# Eagle_Lecture.net
KiCad netlist of a schematic drawn in EAGLE
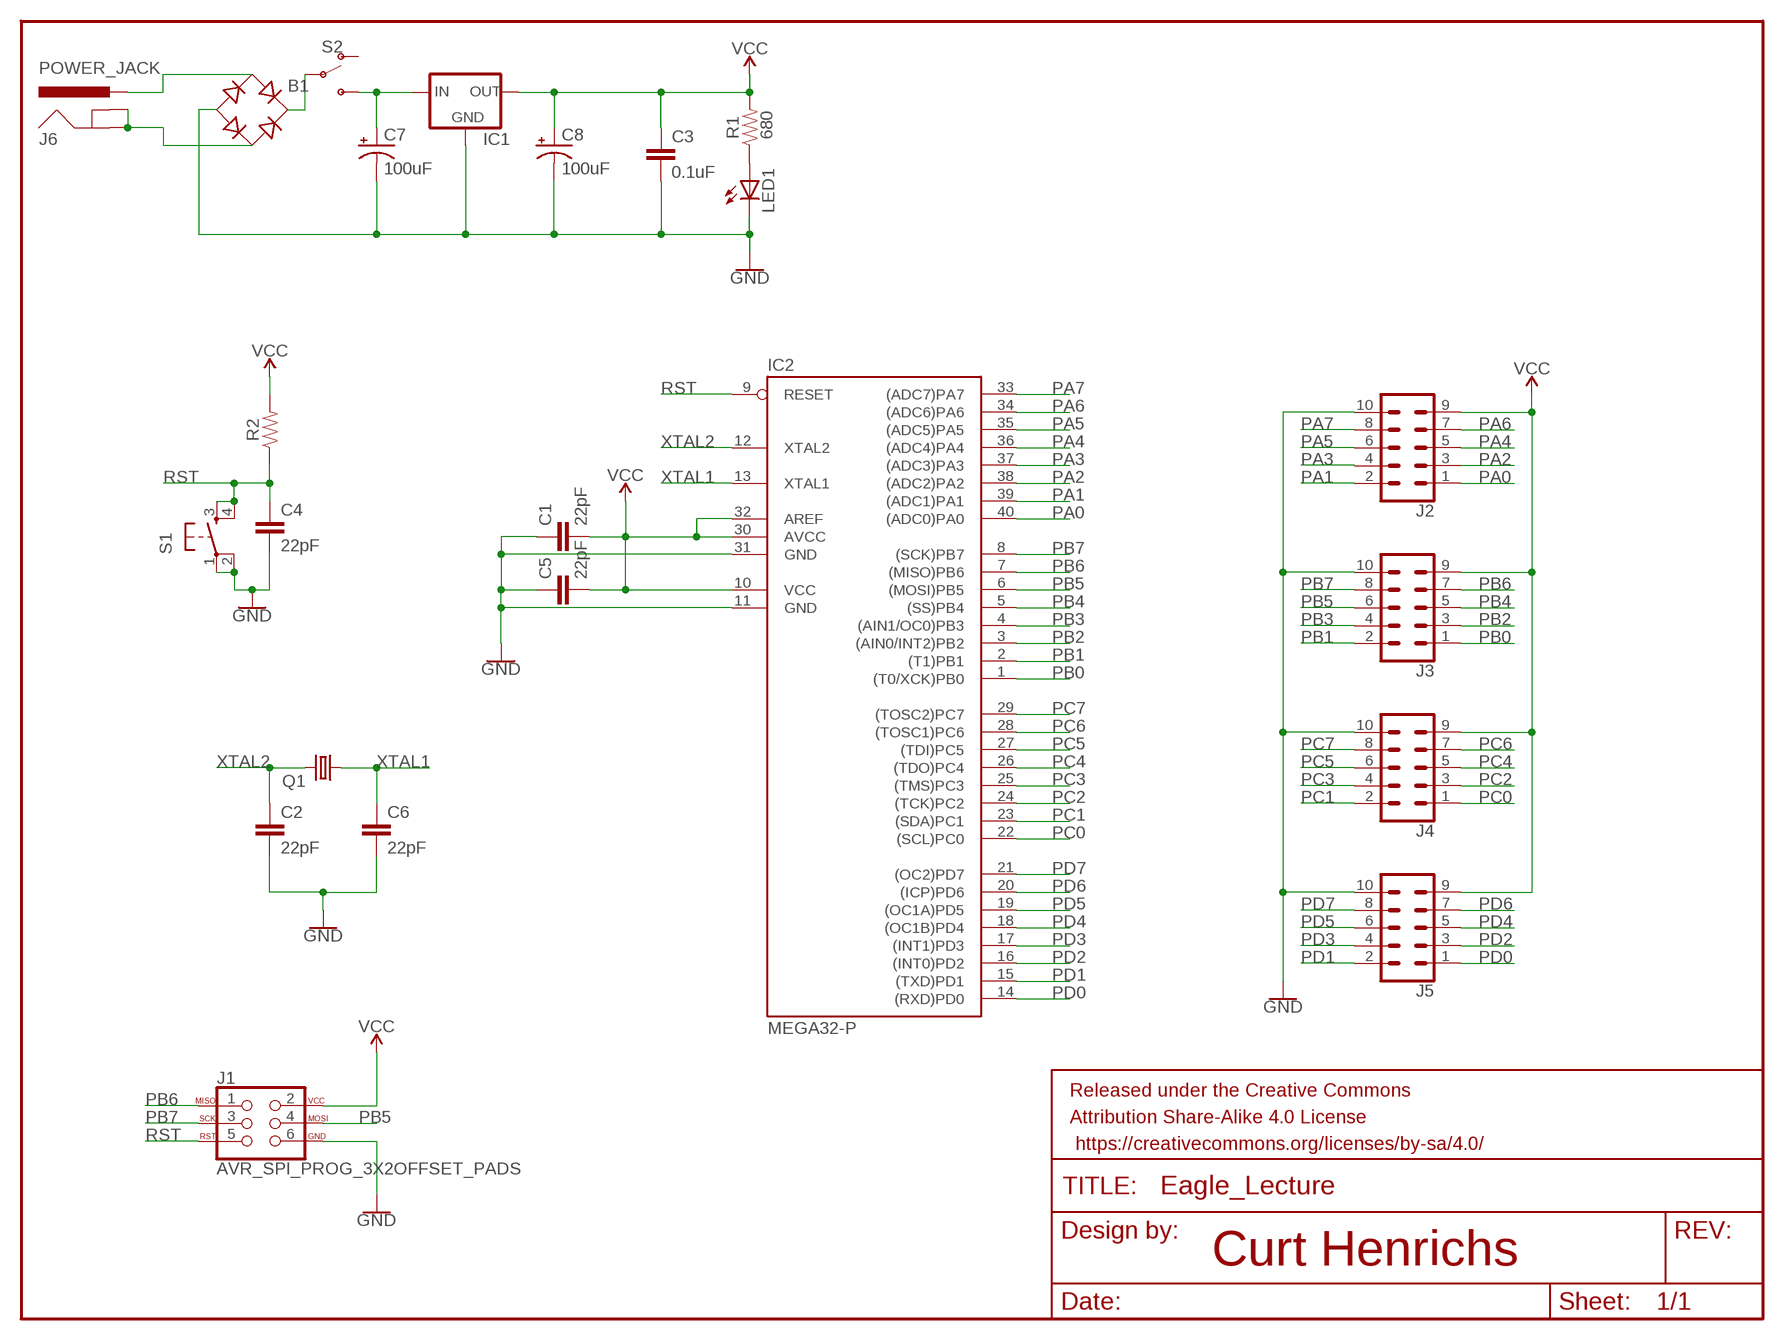
[diagram p0: schematic, sheet 1]

(export (version "E")
  (design (tool "Eeschema 10.0.6"))
  (components
    (comp (ref "B1")
      (value "B-DIL")
      (footprint "eagle-import:B-DIL")
      (libsource (lib "eagle-import") (part "B-DIL"))
    )
    (comp (ref "C1")
      (value "22pF")
      (footprint "eagle-import:CAP-PTH-2.54")
      (libsource (lib "eagle-import") (part "22PF-PTH-2.54MM-200V-5%"))
    )
    (comp (ref "C2")
      (value "22pF")
      (footprint "eagle-import:CAP-PTH-2.54")
      (libsource (lib "eagle-import") (part "22PF-PTH-2.54MM-200V-5%"))
    )
    (comp (ref "C3")
      (value "0.1uF")
      (footprint "eagle-import:CAP-PTH-2.54")
      (libsource (lib "eagle-import") (part "22PF-PTH-2.54MM-200V-5%"))
    )
    (comp (ref "C4")
      (value "22pF")
      (footprint "eagle-import:CAP-PTH-2.54")
      (libsource (lib "eagle-import") (part "22PF-PTH-2.54MM-200V-5%"))
    )
    (comp (ref "C5")
      (value "22pF")
      (footprint "eagle-import:CAP-PTH-2.54")
      (libsource (lib "eagle-import") (part "22PF-PTH-2.54MM-200V-5%"))
    )
    (comp (ref "C6")
      (value "22pF")
      (footprint "eagle-import:CAP-PTH-2.54")
      (libsource (lib "eagle-import") (part "22PF-PTH-2.54MM-200V-5%"))
    )
    (comp (ref "C7")
      (value "100uF")
      (footprint "eagle-import:CPOL-RADIAL-2.5MM-6.5MM")
      (libsource (lib "eagle-import") (part "100UF-POLAR-RADIAL-2.5MM-25V-20%"))
    )
    (comp (ref "C8")
      (value "100uF")
      (footprint "eagle-import:CPOL-RADIAL-2.5MM-6.5MM")
      (libsource (lib "eagle-import") (part "100UF-POLAR-RADIAL-2.5MM-25V-20%"))
    )
    (comp (ref "FRAME1")
      (value "FRAME-LETTER")
      (footprint "eagle-import:CREATIVE_COMMONS")
      (libsource (lib "eagle-import") (part "FRAME-LETTER"))
    )
    (comp (ref "IC1")
      (value "78MXXL")
      (footprint "eagle-import:78MXXL")
      (libsource (lib "eagle-import") (part "78MXXL"))
    )
    (comp (ref "IC2")
      (value "MEGA32-P")
      (footprint "eagle-import:DIL40")
      (fields (field (name "MPN") "ATMEGA32-16PU"))
      (libsource (lib "eagle-import") (part "MEGA32-P"))
    )
    (comp (ref "J1")
      (value "AVR_SPI_PROG_3X2OFFSET_PADS")
      (footprint "eagle-import:2X3_OFFSET")
      (libsource (lib "eagle-import") (part "AVR_SPI_PROG_3X2OFFSET_PADS"))
    )
    (comp (ref "J2")
      (value "CONN_05X2SHD")
      (footprint "eagle-import:2X5-SHROUDED")
      (libsource (lib "eagle-import") (part "CONN_05X2SHD"))
    )
    (comp (ref "J3")
      (value "CONN_05X2SHD")
      (footprint "eagle-import:2X5-SHROUDED")
      (libsource (lib "eagle-import") (part "CONN_05X2SHD"))
    )
    (comp (ref "J4")
      (value "CONN_05X2SHD")
      (footprint "eagle-import:2X5-SHROUDED")
      (libsource (lib "eagle-import") (part "CONN_05X2SHD"))
    )
    (comp (ref "J5")
      (value "CONN_05X2SHD")
      (footprint "eagle-import:2X5-SHROUDED")
      (libsource (lib "eagle-import") (part "CONN_05X2SHD"))
    )
    (comp (ref "J6")
      (value "POWER_JACK")
      (footprint "eagle-import:POWER_JACK_PTH")
      (libsource (lib "eagle-import") (part "POWER_JACK"))
    )
    (comp (ref "LED1")
      (value "LED3MM")
      (footprint "eagle-import:LED3MM")
      (libsource (lib "eagle-import") (part "LED3MM"))
    )
    (comp (ref "Q1")
      (value "CRYSTALHC49U-V")
      (footprint "eagle-import:HC49U-V")
      (libsource (lib "eagle-import") (part "CRYSTALHC49U-V"))
    )
    (comp (ref "R1")
      (value "680")
      (footprint "eagle-import:AXIAL-0.3")
      (libsource (lib "eagle-import") (part "RESISTORAXIAL-0.3"))
    )
    (comp (ref "R2")
      (value "RESISTORAXIAL-0.3")
      (footprint "eagle-import:AXIAL-0.3")
      (libsource (lib "eagle-import") (part "RESISTORAXIAL-0.3"))
    )
    (comp (ref "S1")
      (value "TAC_SWITCHPTH")
      (footprint "eagle-import:TACTILE-PTH")
      (libsource (lib "eagle-import") (part "TAC_SWITCHPTH"))
    )
    (comp (ref "S2")
      (value "SWITCH-SPDT-PTH-11.6X4.0MM")
      (footprint "eagle-import:SWITCH_SPDT_PTH_11.6X4.0MM")
      (libsource (lib "eagle-import") (part "SWITCH-SPDT-PTH-11.6X4.0MM"))
    )
  )
  (nets
    (net (code "1") (name "/PA0") (class "Default")
      (node (ref "IC2") (pin "40") (pinfunction "(ADC0)PA0_40") (pintype "bidirectional"))
      (node (ref "J2") (pin "1") (pinfunction "1_1") (pintype "passive"))
    )
    (net (code "2") (name "/PA1") (class "Default")
      (node (ref "IC2") (pin "39") (pinfunction "(ADC1)PA1_39") (pintype "bidirectional"))
      (node (ref "J2") (pin "2") (pinfunction "2_2") (pintype "passive"))
    )
    (net (code "3") (name "/PA2") (class "Default")
      (node (ref "IC2") (pin "38") (pinfunction "(ADC2)PA2_38") (pintype "bidirectional"))
      (node (ref "J2") (pin "3") (pinfunction "3_3") (pintype "passive"))
    )
    (net (code "4") (name "/PA3") (class "Default")
      (node (ref "IC2") (pin "37") (pinfunction "(ADC3)PA3_37") (pintype "bidirectional"))
      (node (ref "J2") (pin "4") (pinfunction "4_4") (pintype "passive"))
    )
    (net (code "5") (name "/PA4") (class "Default")
      (node (ref "IC2") (pin "36") (pinfunction "(ADC4)PA4_36") (pintype "bidirectional"))
      (node (ref "J2") (pin "5") (pinfunction "5_5") (pintype "passive"))
    )
    (net (code "6") (name "/PA5") (class "Default")
      (node (ref "IC2") (pin "35") (pinfunction "(ADC5)PA5_35") (pintype "bidirectional"))
      (node (ref "J2") (pin "6") (pinfunction "6_6") (pintype "passive"))
    )
    (net (code "7") (name "/PA6") (class "Default")
      (node (ref "IC2") (pin "34") (pinfunction "(ADC6)PA6_34") (pintype "bidirectional"))
      (node (ref "J2") (pin "7") (pinfunction "7_7") (pintype "passive"))
    )
    (net (code "8") (name "/PA7") (class "Default")
      (node (ref "IC2") (pin "33") (pinfunction "(ADC7)PA7_33") (pintype "bidirectional"))
      (node (ref "J2") (pin "8") (pinfunction "8_8") (pintype "passive"))
    )
    (net (code "9") (name "/PB0") (class "Default")
      (node (ref "IC2") (pin "1") (pinfunction "(T0/XCK)PB0_1") (pintype "bidirectional"))
      (node (ref "J3") (pin "1") (pinfunction "1_1") (pintype "passive"))
    )
    (net (code "10") (name "/PB1") (class "Default")
      (node (ref "IC2") (pin "2") (pinfunction "(T1)PB1_2") (pintype "bidirectional"))
      (node (ref "J3") (pin "2") (pinfunction "2_2") (pintype "passive"))
    )
    (net (code "11") (name "/PB2") (class "Default")
      (node (ref "IC2") (pin "3") (pinfunction "(AIN0/INT2)PB2_3") (pintype "bidirectional"))
      (node (ref "J3") (pin "3") (pinfunction "3_3") (pintype "passive"))
    )
    (net (code "12") (name "/PB3") (class "Default")
      (node (ref "IC2") (pin "4") (pinfunction "(AIN1/OC0)PB3_4") (pintype "bidirectional"))
      (node (ref "J3") (pin "4") (pinfunction "4_4") (pintype "passive"))
    )
    (net (code "13") (name "/PB4") (class "Default")
      (node (ref "IC2") (pin "5") (pinfunction "(SS)PB4_5") (pintype "bidirectional"))
      (node (ref "J3") (pin "5") (pinfunction "5_5") (pintype "passive"))
    )
    (net (code "14") (name "/PB5") (class "Default")
      (node (ref "IC2") (pin "6") (pinfunction "(MOSI)PB5_6") (pintype "bidirectional"))
      (node (ref "J1") (pin "4") (pinfunction "4_4") (pintype "passive"))
      (node (ref "J3") (pin "6") (pinfunction "6_6") (pintype "passive"))
    )
    (net (code "15") (name "/PB6") (class "Default")
      (node (ref "IC2") (pin "7") (pinfunction "(MISO)PB6_7") (pintype "bidirectional"))
      (node (ref "J1") (pin "1") (pinfunction "1_1") (pintype "passive"))
      (node (ref "J3") (pin "7") (pinfunction "7_7") (pintype "passive"))
    )
    (net (code "16") (name "/PB7") (class "Default")
      (node (ref "IC2") (pin "8") (pinfunction "(SCK)PB7_8") (pintype "bidirectional"))
      (node (ref "J1") (pin "3") (pinfunction "3_3") (pintype "passive"))
      (node (ref "J3") (pin "8") (pinfunction "8_8") (pintype "passive"))
    )
    (net (code "17") (name "/PC0") (class "Default")
      (node (ref "IC2") (pin "22") (pinfunction "(SCL)PC0_22") (pintype "bidirectional"))
      (node (ref "J4") (pin "1") (pinfunction "1_1") (pintype "passive"))
    )
    (net (code "18") (name "/PC1") (class "Default")
      (node (ref "IC2") (pin "23") (pinfunction "(SDA)PC1_23") (pintype "bidirectional"))
      (node (ref "J4") (pin "2") (pinfunction "2_2") (pintype "passive"))
    )
    (net (code "19") (name "/PC2") (class "Default")
      (node (ref "IC2") (pin "24") (pinfunction "(TCK)PC2_24") (pintype "bidirectional"))
      (node (ref "J4") (pin "3") (pinfunction "3_3") (pintype "passive"))
    )
    (net (code "20") (name "/PC3") (class "Default")
      (node (ref "IC2") (pin "25") (pinfunction "(TMS)PC3_25") (pintype "bidirectional"))
      (node (ref "J4") (pin "4") (pinfunction "4_4") (pintype "passive"))
    )
    (net (code "21") (name "/PC4") (class "Default")
      (node (ref "IC2") (pin "26") (pinfunction "(TDO)PC4_26") (pintype "bidirectional"))
      (node (ref "J4") (pin "5") (pinfunction "5_5") (pintype "passive"))
    )
    (net (code "22") (name "/PC5") (class "Default")
      (node (ref "IC2") (pin "27") (pinfunction "(TDI)PC5_27") (pintype "bidirectional"))
      (node (ref "J4") (pin "6") (pinfunction "6_6") (pintype "passive"))
    )
    (net (code "23") (name "/PC6") (class "Default")
      (node (ref "IC2") (pin "28") (pinfunction "(TOSC1)PC6_28") (pintype "bidirectional"))
      (node (ref "J4") (pin "7") (pinfunction "7_7") (pintype "passive"))
    )
    (net (code "24") (name "/PC7") (class "Default")
      (node (ref "IC2") (pin "29") (pinfunction "(TOSC2)PC7_29") (pintype "bidirectional"))
      (node (ref "J4") (pin "8") (pinfunction "8_8") (pintype "passive"))
    )
    (net (code "25") (name "/PD0") (class "Default")
      (node (ref "IC2") (pin "14") (pinfunction "(RXD)PD0_14") (pintype "bidirectional"))
      (node (ref "J5") (pin "1") (pinfunction "1_1") (pintype "passive"))
    )
    (net (code "26") (name "/PD1") (class "Default")
      (node (ref "IC2") (pin "15") (pinfunction "(TXD)PD1_15") (pintype "bidirectional"))
      (node (ref "J5") (pin "2") (pinfunction "2_2") (pintype "passive"))
    )
    (net (code "27") (name "/PD2") (class "Default")
      (node (ref "IC2") (pin "16") (pinfunction "(INT0)PD2_16") (pintype "bidirectional"))
      (node (ref "J5") (pin "3") (pinfunction "3_3") (pintype "passive"))
    )
    (net (code "28") (name "/PD3") (class "Default")
      (node (ref "IC2") (pin "17") (pinfunction "(INT1)PD3_17") (pintype "bidirectional"))
      (node (ref "J5") (pin "4") (pinfunction "4_4") (pintype "passive"))
    )
    (net (code "29") (name "/PD4") (class "Default")
      (node (ref "IC2") (pin "18") (pinfunction "(OC1B)PD4_18") (pintype "bidirectional"))
      (node (ref "J5") (pin "5") (pinfunction "5_5") (pintype "passive"))
    )
    (net (code "30") (name "/PD5") (class "Default")
      (node (ref "IC2") (pin "19") (pinfunction "(OC1A)PD5_19") (pintype "bidirectional"))
      (node (ref "J5") (pin "6") (pinfunction "6_6") (pintype "passive"))
    )
    (net (code "31") (name "/PD6") (class "Default")
      (node (ref "IC2") (pin "20") (pinfunction "(ICP)PD6_20") (pintype "bidirectional"))
      (node (ref "J5") (pin "7") (pinfunction "7_7") (pintype "passive"))
    )
    (net (code "32") (name "/PD7") (class "Default")
      (node (ref "IC2") (pin "21") (pinfunction "(OC2)PD7_21") (pintype "bidirectional"))
      (node (ref "J5") (pin "8") (pinfunction "8_8") (pintype "passive"))
    )
    (net (code "33") (name "/RST") (class "Default")
      (node (ref "C4") (pin "1") (pinfunction "1_1") (pintype "passive"))
      (node (ref "IC2") (pin "9") (pinfunction "RESET_9") (pintype "input"))
      (node (ref "J1") (pin "5") (pinfunction "5_5") (pintype "passive"))
      (node (ref "R2") (pin "P$1") (pinfunction "1_P$1") (pintype "passive"))
      (node (ref "S1") (pin "3") (pinfunction "3_3") (pintype "passive"))
      (node (ref "S1") (pin "4") (pinfunction "4_4") (pintype "passive"))
    )
    (net (code "34") (name "/XTAL1") (class "Default")
      (node (ref "C6") (pin "1") (pinfunction "1_1") (pintype "passive"))
      (node (ref "IC2") (pin "13") (pinfunction "XTAL1_13") (pintype "bidirectional"))
      (node (ref "Q1") (pin "1") (pinfunction "1_1") (pintype "passive"))
    )
    (net (code "35") (name "/XTAL2") (class "Default")
      (node (ref "C2") (pin "1") (pinfunction "1_1") (pintype "passive"))
      (node (ref "IC2") (pin "12") (pinfunction "XTAL2_12") (pintype "bidirectional"))
      (node (ref "Q1") (pin "2") (pinfunction "2_2") (pintype "passive"))
    )
    (net (code "36") (name "GND") (class "Default")
      (node (ref "B1") (pin "-") (pinfunction "-_-") (pintype "passive"))
      (node (ref "C1") (pin "1") (pinfunction "1_1") (pintype "passive"))
      (node (ref "C2") (pin "2") (pinfunction "2_2") (pintype "passive"))
      (node (ref "C3") (pin "2") (pinfunction "2_2") (pintype "passive"))
      (node (ref "C4") (pin "2") (pinfunction "2_2") (pintype "passive"))
      (node (ref "C5") (pin "1") (pinfunction "1_1") (pintype "passive"))
      (node (ref "C6") (pin "2") (pinfunction "2_2") (pintype "passive"))
      (node (ref "C7") (pin "2") (pinfunction "-_2") (pintype "passive"))
      (node (ref "C8") (pin "2") (pinfunction "-_2") (pintype "passive"))
      (node (ref "IC1") (pin "GND") (pinfunction "GND_GND") (pintype "input"))
      (node (ref "IC2") (pin "11") (pinfunction "GND_11") (pintype "power_in"))
      (node (ref "IC2") (pin "31") (pinfunction "GND_31") (pintype "power_in"))
      (node (ref "J1") (pin "6") (pinfunction "6_6") (pintype "passive"))
      (node (ref "J2") (pin "10") (pinfunction "10_10") (pintype "passive"))
      (node (ref "J3") (pin "10") (pinfunction "10_10") (pintype "passive"))
      (node (ref "J4") (pin "10") (pinfunction "10_10") (pintype "passive"))
      (node (ref "J5") (pin "10") (pinfunction "10_10") (pintype "passive"))
      (node (ref "LED1") (pin "K") (pinfunction "C_K") (pintype "passive"))
      (node (ref "S1") (pin "1") (pinfunction "1_1") (pintype "passive"))
      (node (ref "S1") (pin "2") (pinfunction "2_2") (pintype "passive"))
    )
    (net (code "37") (name "Net-(B1-PadAC1)") (class "Default")
      (node (ref "B1") (pin "AC1") (pinfunction "AC1_AC1") (pintype "passive"))
      (node (ref "J6") (pin "PWR") (pinfunction "PWR_PWR") (pintype "bidirectional"))
    )
    (net (code "38") (name "Net-(B1-PadAC2)") (class "Default")
      (node (ref "B1") (pin "AC2") (pinfunction "AC2_AC2") (pintype "passive"))
      (node (ref "J6") (pin "GND") (pinfunction "GND_GND") (pintype "bidirectional"))
      (node (ref "J6") (pin "GNDBREAK") (pinfunction "GNDBREAK_GNDBREAK") (pintype "bidirectional"))
    )
    (net (code "39") (name "Net-(C7-+)") (class "Default")
      (node (ref "C7") (pin "1") (pinfunction "+_1") (pintype "passive"))
      (node (ref "IC1") (pin "IN") (pinfunction "IN_IN") (pintype "input"))
      (node (ref "S2") (pin "3") (pinfunction "S_3") (pintype "passive"))
    )
    (net (code "40") (name "Net-(R1-1)") (class "Default")
      (node (ref "LED1") (pin "A") (pinfunction "A_A") (pintype "passive"))
      (node (ref "R1") (pin "P$1") (pinfunction "1_P$1") (pintype "passive"))
    )
    (net (code "41") (name "Net-(S2-P)") (class "Default")
      (node (ref "B1") (pin "+") (pinfunction "+_+") (pintype "passive"))
      (node (ref "S2") (pin "2") (pinfunction "P_2") (pintype "passive"))
    )
    (net (code "42") (name "VCC") (class "Default")
      (node (ref "C1") (pin "2") (pinfunction "2_2") (pintype "passive"))
      (node (ref "C3") (pin "1") (pinfunction "1_1") (pintype "passive"))
      (node (ref "C5") (pin "2") (pinfunction "2_2") (pintype "passive"))
      (node (ref "C8") (pin "1") (pinfunction "+_1") (pintype "passive"))
      (node (ref "IC1") (pin "OUT") (pinfunction "OUT_OUT") (pintype "passive"))
      (node (ref "IC2") (pin "10") (pinfunction "VCC_10") (pintype "power_in"))
      (node (ref "IC2") (pin "30") (pinfunction "AVCC_30") (pintype "power_in"))
      (node (ref "IC2") (pin "32") (pinfunction "AREF_32") (pintype "passive"))
      (node (ref "J1") (pin "2") (pinfunction "2_2") (pintype "passive"))
      (node (ref "J2") (pin "9") (pinfunction "9_9") (pintype "passive"))
      (node (ref "J3") (pin "9") (pinfunction "9_9") (pintype "passive"))
      (node (ref "J4") (pin "9") (pinfunction "9_9") (pintype "passive"))
      (node (ref "J5") (pin "9") (pinfunction "9_9") (pintype "passive"))
      (node (ref "R1") (pin "P$2") (pinfunction "2_P$2") (pintype "passive"))
      (node (ref "R2") (pin "P$2") (pinfunction "2_P$2") (pintype "passive"))
    )
    (net (code "43") (name "unconnected-(S2-O-Pad1)") (class "Default")
      (node (ref "S2") (pin "1") (pinfunction "O_1") (pintype "passive"))
    )
  )
)
